# nufsr-rs485.net
KiCad netlist of a schematic drawn in Altium Designer
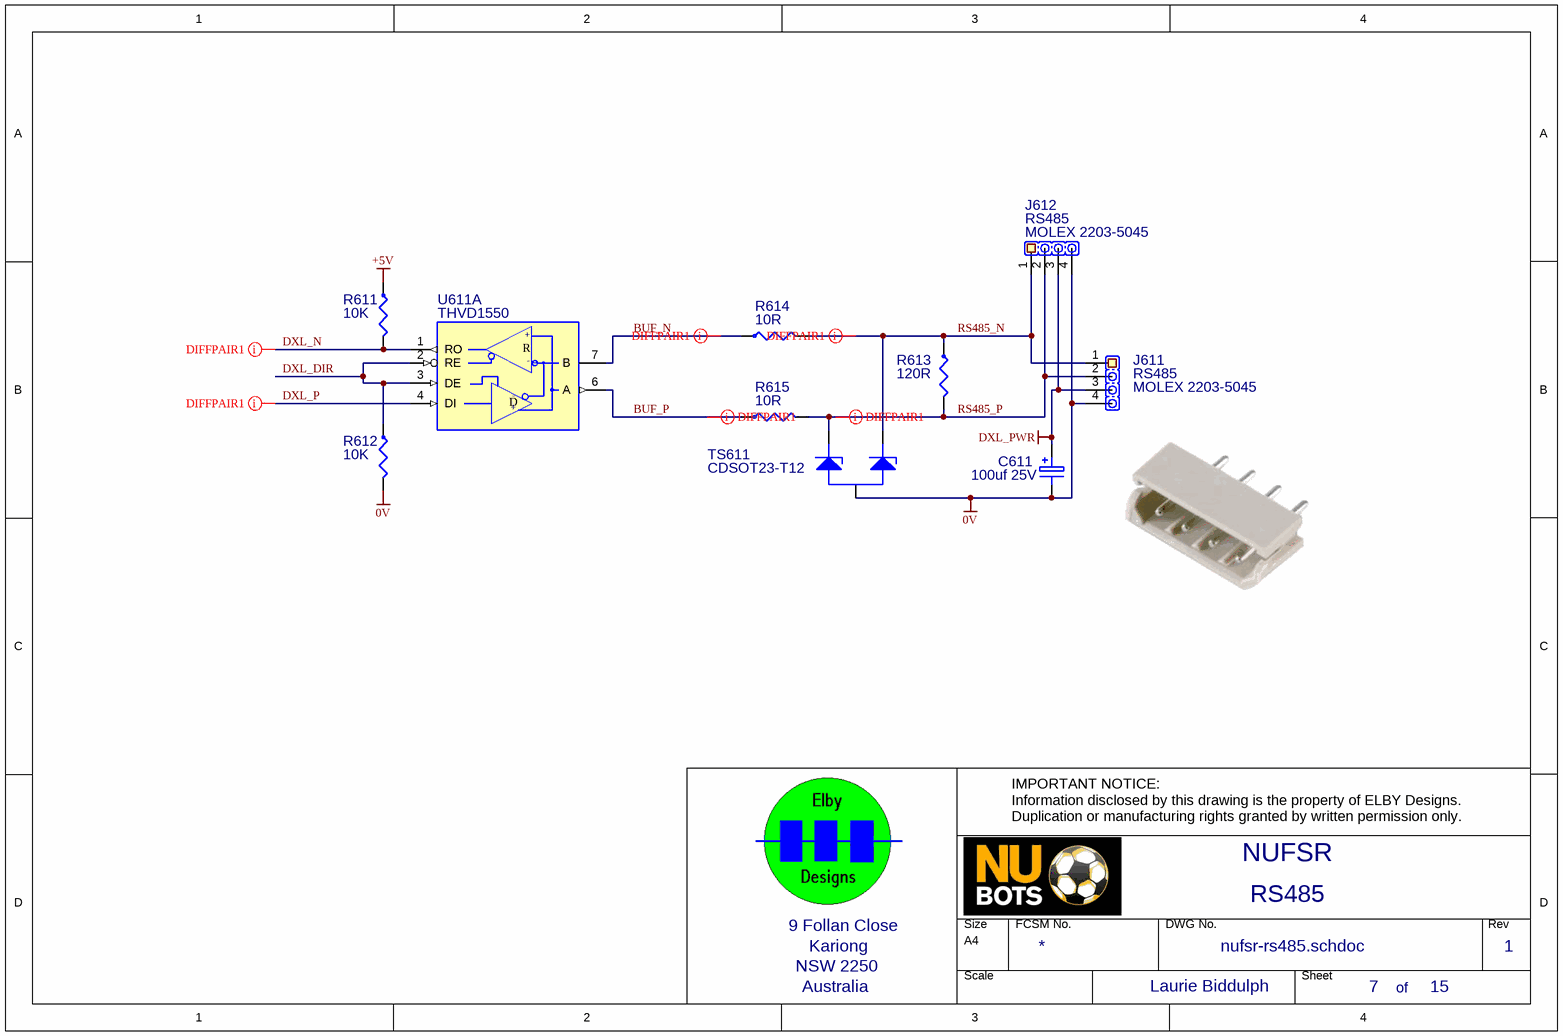
[diagram p0: nufsr-rs485.schdoc]

(export (version "E")
  (design (tool "Eeschema 10.0.6"))
  (components
    (comp (ref "C611")
      (value "100uf 25V")
      (footprint "RB-D6.3-P2.5")
      (description "20% 50V Aluminium Electrolytic")
      (libsource (lib "capacitor") (part "CE-100UF50V(LB)"))
    )
    (comp (ref "J611")
      (value "RS485")
      (footprint "CON-MOLEX_2203-5045")
      (description "1x4 Header")
      (fields (field (name "PART") "MOLEX 2203-5045"))
      (libsource (lib "connectors") (part "HEADER-1X4"))
    )
    (comp (ref "J612")
      (value "RS485")
      (footprint "CON-MOLEX_2203-5045")
      (description "1x4 Header")
      (fields (field (name "PART") "MOLEX 2203-5045"))
      (libsource (lib "") (part "HEADER-1X4_1"))
    )
    (comp (ref "R611")
      (value "10K")
      (footprint "0603(LB)")
      (description "0.5W 1% Metal Film Resistor")
      (libsource (lib "resistor") (part "RM-10K(LB)"))
    )
    (comp (ref "R612")
      (value "10K")
      (footprint "0603(LB)")
      (description "0.5W 1% Metal Film Resistor")
      (libsource (lib "resistor") (part "RM-10K(LB)"))
    )
    (comp (ref "R613")
      (value "120R")
      (footprint "0603(LB)")
      (description "0.5W 1% Metal Film Resistor")
      (libsource (lib "resistor") (part "RM-120R(LB)"))
    )
    (comp (ref "R614")
      (value "10R")
      (footprint "0603(LB)")
      (description "10R Pulse-proof")
      (libsource (lib "NuBots") (part "RP-10R(LB)"))
    )
    (comp (ref "R615")
      (value "10R")
      (footprint "0603(LB)")
      (description "10R Pulse-proof")
      (libsource (lib "NuBots") (part "RP-10R(LB)"))
    )
    (comp (ref "TS611")
      (value "CDSOT23-T12")
      (footprint "SOT-23-3(LB)")
      (description "600V Bi-directional Transient Suppressor")
      (libsource (lib "NuBots") (part "CDSOT23-T12(LB)"))
    )
    (comp (ref "U611")
      (value "THVD1550")
      (footprint "SO-8(LB)")
      (description "RS485 Transceiver 18kV 50mbps")
      (libsource (lib "NuBots") (part "THVD1550(LB)"))
    )
  )
  (nets
    (net (code "1") (name "+5V") (class "Default")
      (node (ref "R611") (pin "1") (pinfunction "1_1") (pintype "passive"))
    )
    (net (code "2") (name "/BUF_N") (class "Default")
      (node (ref "R614") (pin "1") (pinfunction "1_1") (pintype "passive"))
      (node (ref "U611") (pin "7") (pinfunction "B_7") (pintype "passive"))
    )
    (net (code "3") (name "/BUF_P") (class "Default")
      (node (ref "R615") (pin "1") (pinfunction "1_1") (pintype "passive"))
      (node (ref "U611") (pin "6") (pinfunction "A_6") (pintype "output"))
    )
    (net (code "4") (name "/DXL_DIR") (class "Default")
      (node (ref "R612") (pin "1") (pinfunction "1_1") (pintype "passive"))
      (node (ref "U611") (pin "2") (pinfunction "RE_2") (pintype "input"))
      (node (ref "U611") (pin "3") (pinfunction "DE_3") (pintype "input"))
    )
    (net (code "5") (name "/DXL_N") (class "Default")
      (node (ref "R611") (pin "2") (pinfunction "2_2") (pintype "passive"))
      (node (ref "U611") (pin "1") (pinfunction "RO_1") (pintype "output"))
    )
    (net (code "6") (name "/DXL_P") (class "Default")
      (node (ref "U611") (pin "4") (pinfunction "DI_4") (pintype "input"))
    )
    (net (code "7") (name "/RS485_N") (class "Default")
      (node (ref "J611") (pin "1") (pinfunction "1_1") (pintype "passive"))
      (node (ref "J612") (pin "1") (pinfunction "1_1") (pintype "passive"))
      (node (ref "R613") (pin "1") (pinfunction "1_1") (pintype "passive"))
      (node (ref "R614") (pin "2") (pinfunction "2_2") (pintype "passive"))
      (node (ref "TS611") (pin "1") (pinfunction "1_1") (pintype "passive"))
    )
    (net (code "8") (name "/RS485_P") (class "Default")
      (node (ref "J611") (pin "2") (pinfunction "2_2") (pintype "passive"))
      (node (ref "J612") (pin "2") (pinfunction "2_2") (pintype "passive"))
      (node (ref "R613") (pin "2") (pinfunction "2_2") (pintype "passive"))
      (node (ref "R615") (pin "2") (pinfunction "2_2") (pintype "passive"))
      (node (ref "TS611") (pin "2") (pinfunction "2_2") (pintype "passive"))
    )
    (net (code "9") (name "0V") (class "Default")
      (node (ref "C611") (pin "2") (pintype "passive"))
      (node (ref "J611") (pin "4") (pinfunction "4_4") (pintype "passive"))
      (node (ref "J612") (pin "4") (pinfunction "4_4") (pintype "passive"))
      (node (ref "R612") (pin "2") (pinfunction "2_2") (pintype "passive"))
      (node (ref "TS611") (pin "3") (pinfunction "3_3") (pintype "passive"))
    )
    (net (code "10") (name "DXL_PWR") (class "Default")
      (node (ref "C611") (pin "1") (pintype "passive"))
      (node (ref "J611") (pin "3") (pinfunction "3_3") (pintype "passive"))
      (node (ref "J612") (pin "3") (pinfunction "3_3") (pintype "passive"))
    )
  )
)
